# ncp5623c-breakout.net
KiCad netlist of a schematic drawn in EAGLE
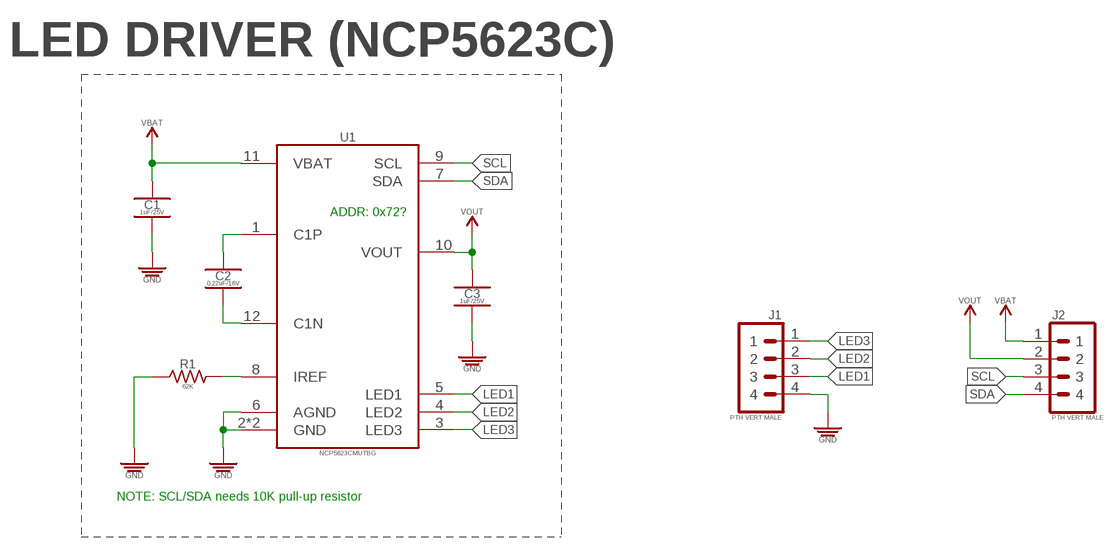
[diagram p0: schematic, sheet 1]

(export (version "E")
  (design (tool "Eeschema 10.0.6"))
  (components
    (comp (ref "C1")
      (value "1uF/25V")
      (footprint "eagle-import:CAPC1005X55_SMD-0402")
      (fields (field (name "MFR") "TDK Corporation") (field (name "MPN") "CGB2A1X5R1E105K033BC"))
      (libsource (lib "eagle-import") (part "1UF_CER_SMD-0402_25V-10%"))
    )
    (comp (ref "C2")
      (value "0.22uF/16V")
      (footprint "eagle-import:CAPC1005X55_SMD-0402")
      (fields (field (name "MFR") "TDK Corporation") (field (name "MPN") "CGA2B1X5R1C224K050BC"))
      (libsource (lib "eagle-import") (part "0.22UF_CER_SMD_0402_16V-10%"))
    )
    (comp (ref "C3")
      (value "1uF/25V")
      (footprint "eagle-import:CAPC1005X55_SMD-0402")
      (fields (field (name "MFR") "TDK Corporation") (field (name "MPN") "CGB2A1X5R1E105K033BC"))
      (libsource (lib "eagle-import") (part "1UF_CER_SMD-0402_25V-10%"))
    )
    (comp (ref "J1")
      (value "PTH VERT MALE")
      (footprint "eagle-import:HDRV4W64P254_1X4_1016X254X838B")
      (fields (field (name "MFR") "Sullins Connector Solutions") (field (name "MPN") "PEC04SAAN"))
      (libsource (lib "eagle-import") (part "1X04_PTH_VERT_MALE_2.54MM"))
    )
    (comp (ref "J2")
      (value "PTH VERT MALE")
      (footprint "eagle-import:HDRV4W64P254_1X4_1016X254X838B")
      (fields (field (name "MFR") "Sullins Connector Solutions") (field (name "MPN") "PEC04SAAN"))
      (libsource (lib "eagle-import") (part "1X04_PTH_VERT_MALE_2.54MM"))
    )
    (comp (ref "R1")
      (value "62K")
      (footprint "eagle-import:RESC1005X35_SMD-0402")
      (fields (field (name "MFR") "Yageo") (field (name "MPN") "RC0402JR-0762KL"))
      (libsource (lib "eagle-import") (part "62KΩ_SMD-0402_1/16W-5%"))
    )
    (comp (ref "U1")
      (value "NCP5623CMUTBG")
      (footprint "eagle-import:SON40P200X200X80-11T57X90N")
      (fields (field (name "MFR") "ON Semiconductor"))
      (libsource (lib "eagle-import") (part "NCP5623CMUTBG"))
    )
  )
  (nets
    (net (code "1") (name "GND") (class "Default")
      (node (ref "C1") (pin "2") (pinfunction "2_2") (pintype "passive"))
      (node (ref "C3") (pin "2") (pinfunction "2_2") (pintype "passive"))
      (node (ref "J1") (pin "4") (pinfunction "4_4") (pintype "passive"))
      (node (ref "R1") (pin "1") (pinfunction "1_1") (pintype "passive"))
      (node (ref "U1") (pin "2") (pinfunction "GND_2") (pintype "power_in"))
      (node (ref "U1") (pin "6") (pinfunction "AGND_6") (pintype "power_in"))
      (node (ref "U1") (pin "EP") (pinfunction "GND_EP") (pintype "power_in"))
    )
    (net (code "2") (name "LED1") (class "Default")
      (node (ref "J1") (pin "3") (pinfunction "3_3") (pintype "passive"))
      (node (ref "U1") (pin "5") (pinfunction "LED1_5") (pintype "bidirectional"))
    )
    (net (code "3") (name "LED2") (class "Default")
      (node (ref "J1") (pin "2") (pinfunction "2_2") (pintype "passive"))
      (node (ref "U1") (pin "4") (pinfunction "LED2_4") (pintype "bidirectional"))
    )
    (net (code "4") (name "LED3") (class "Default")
      (node (ref "J1") (pin "1") (pinfunction "1_1") (pintype "passive"))
      (node (ref "U1") (pin "3") (pinfunction "LED3_3") (pintype "bidirectional"))
    )
    (net (code "5") (name "Net-(U1-C1N)") (class "Default")
      (node (ref "C2") (pin "2") (pinfunction "2_2") (pintype "passive"))
      (node (ref "U1") (pin "12") (pinfunction "C1N_12") (pintype "bidirectional"))
    )
    (net (code "6") (name "Net-(U1-C1P)") (class "Default")
      (node (ref "C2") (pin "1") (pinfunction "1_1") (pintype "passive"))
      (node (ref "U1") (pin "1") (pinfunction "C1P_1") (pintype "bidirectional"))
    )
    (net (code "7") (name "Net-(U1-IREF)") (class "Default")
      (node (ref "R1") (pin "2") (pinfunction "2_2") (pintype "passive"))
      (node (ref "U1") (pin "8") (pinfunction "IREF_8") (pintype "bidirectional"))
    )
    (net (code "8") (name "SCL") (class "Default")
      (node (ref "J2") (pin "3") (pinfunction "3_3") (pintype "passive"))
      (node (ref "U1") (pin "9") (pinfunction "SCL_9") (pintype "bidirectional"))
    )
    (net (code "9") (name "SDA") (class "Default")
      (node (ref "J2") (pin "4") (pinfunction "4_4") (pintype "passive"))
      (node (ref "U1") (pin "7") (pinfunction "SDA_7") (pintype "bidirectional"))
    )
    (net (code "10") (name "VBAT") (class "Default")
      (node (ref "C1") (pin "1") (pinfunction "1_1") (pintype "passive"))
      (node (ref "J2") (pin "1") (pinfunction "1_1") (pintype "passive"))
      (node (ref "U1") (pin "11") (pinfunction "VBAT_11") (pintype "power_in"))
    )
    (net (code "11") (name "VOUT") (class "Default")
      (node (ref "C3") (pin "1") (pinfunction "1_1") (pintype "passive"))
      (node (ref "J2") (pin "2") (pinfunction "2_2") (pintype "passive"))
      (node (ref "U1") (pin "10") (pinfunction "VOUT_10") (pintype "power_in"))
    )
  )
)
